# sensor_card.net
KiCad netlist of a schematic drawn in EAGLE
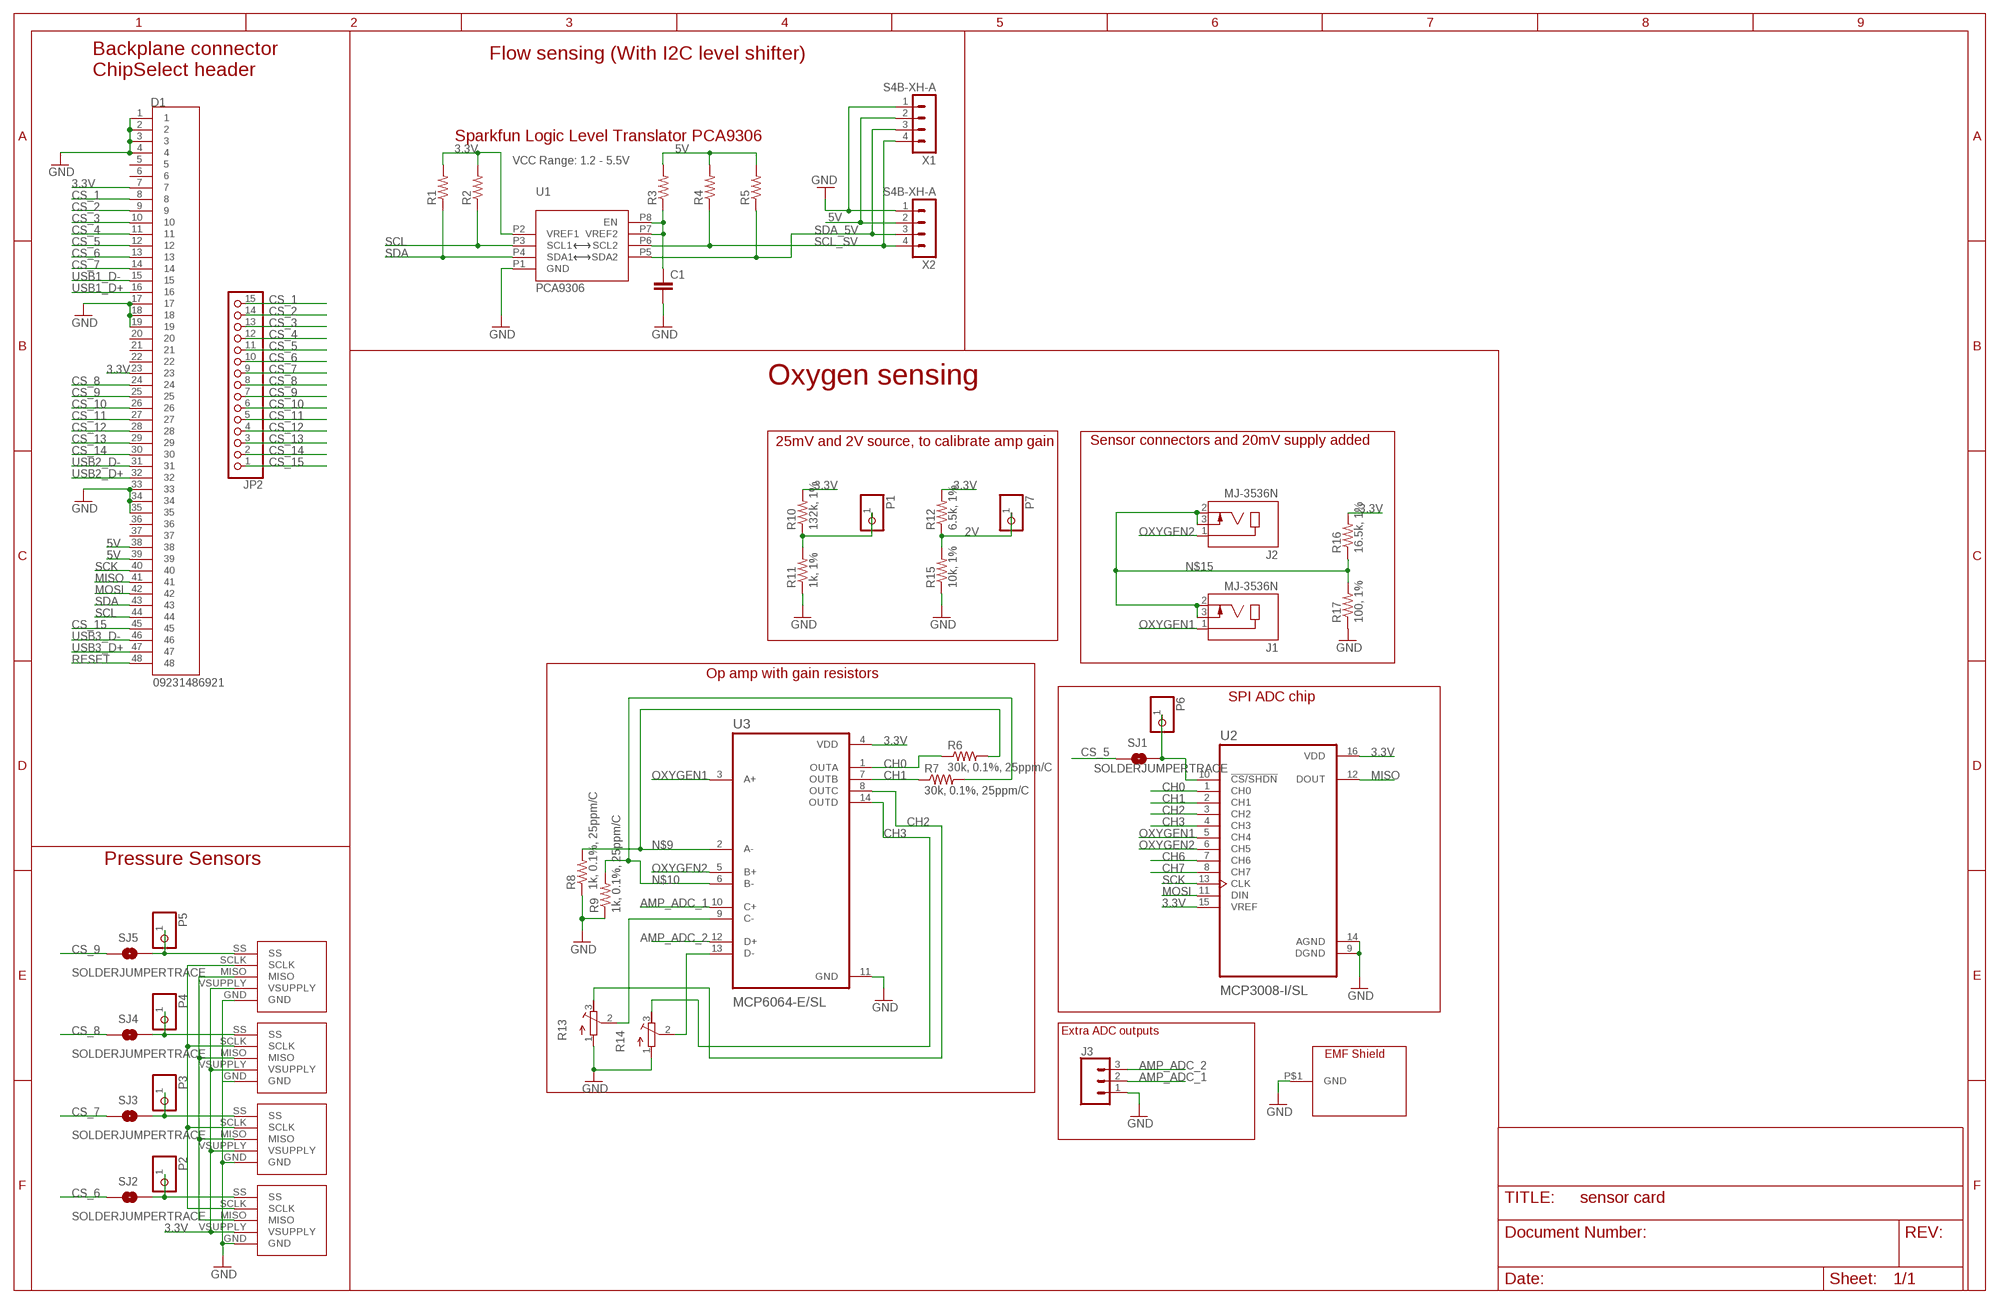
[diagram p0: schematic, sheet 1]

(export (version "E")
  (design (tool "Eeschema 10.0.6"))
  (components
    (comp (ref "C1")
      (value "100pF")
      (footprint "eagle-import:0805")
      (libsource (lib "eagle-import") (part "CAP0805"))
    )
    (comp (ref "D1")
      (value "09231486921")
      (footprint "eagle-import:HARTING_09231486921")
      (libsource (lib "eagle-import") (part "09231486921"))
    )
    (comp (ref "J1")
      (value "MJ-3536N")
      (footprint "eagle-import:CUI_MJ-3536N")
      (libsource (lib "eagle-import") (part "MJ-3536N"))
    )
    (comp (ref "J2")
      (value "MJ-3536N")
      (footprint "eagle-import:CUI_MJ-3536N")
      (libsource (lib "eagle-import") (part "MJ-3536N"))
    )
    (comp (ref "J3")
      (value "CONN_03")
      (footprint "eagle-import:1X03")
      (libsource (lib "eagle-import") (part "CONN_03"))
    )
    (comp (ref "JP2")
      (value "PINHD-1X15")
      (footprint "eagle-import:1X15")
      (libsource (lib "eagle-import") (part "PINHD-1X15"))
    )
    (comp (ref "P1")
      (value "PINHD-1X1")
      (footprint "eagle-import:1X01")
      (libsource (lib "eagle-import") (part "PINHD-1X1"))
    )
    (comp (ref "P2")
      (value "PINHD-1X1")
      (footprint "eagle-import:1X01")
      (libsource (lib "eagle-import") (part "PINHD-1X1"))
    )
    (comp (ref "P3")
      (value "PINHD-1X1")
      (footprint "eagle-import:1X01")
      (libsource (lib "eagle-import") (part "PINHD-1X1"))
    )
    (comp (ref "P4")
      (value "PINHD-1X1")
      (footprint "eagle-import:1X01")
      (libsource (lib "eagle-import") (part "PINHD-1X1"))
    )
    (comp (ref "P5")
      (value "PINHD-1X1")
      (footprint "eagle-import:1X01")
      (libsource (lib "eagle-import") (part "PINHD-1X1"))
    )
    (comp (ref "P6")
      (value "PINHD-1X1")
      (footprint "eagle-import:1X01")
      (libsource (lib "eagle-import") (part "PINHD-1X1"))
    )
    (comp (ref "P7")
      (value "PINHD-1X1")
      (footprint "eagle-import:1X01")
      (libsource (lib "eagle-import") (part "PINHD-1X1"))
    )
    (comp (ref "R1")
      (value "2.2k")
      (footprint "eagle-import:0805")
      (libsource (lib "eagle-import") (part "RESISTOR0805-RES"))
    )
    (comp (ref "R2")
      (value "2.2k")
      (footprint "eagle-import:0805")
      (libsource (lib "eagle-import") (part "RESISTOR0805-RES"))
    )
    (comp (ref "R3")
      (value "200K")
      (footprint "eagle-import:0805")
      (libsource (lib "eagle-import") (part "RESISTOR0805-RES"))
    )
    (comp (ref "R4")
      (value "2.2k")
      (footprint "eagle-import:0805")
      (libsource (lib "eagle-import") (part "RESISTOR0805-RES"))
    )
    (comp (ref "R5")
      (value "2.2k")
      (footprint "eagle-import:0805")
      (libsource (lib "eagle-import") (part "RESISTOR0805-RES"))
    )
    (comp (ref "R6")
      (value "30k, 0.1%, 25ppm/C")
      (footprint "eagle-import:0805")
      (fields
        (field (name "MANUFACTURER-PART-NUMBER") "ERA-6ARB303V")
        (field (name "SIMILAR-COMPONENTS") "Vishay precision resistors or anything else that fits the spec")
      )
      (libsource (lib "eagle-import") (part "RESISTOR0805-RES"))
    )
    (comp (ref "R7")
      (value "30k, 0.1%, 25ppm/C")
      (footprint "eagle-import:0805")
      (fields (field (name "MANUFACTURER-PART-NUMBER") "ERA-6ARB303V"))
      (libsource (lib "eagle-import") (part "RESISTOR0805-RES"))
    )
    (comp (ref "R8")
      (value "1k, 0.1%, 25ppm/C")
      (footprint "eagle-import:0805")
      (fields
        (field (name "MANUFACTURER-PART-NUMBER") "ERA-6ARB102V")
        (field (name "SIMILAR-COMPONENTS") "Vishay precision resistors or anything else that fits the spec")
      )
      (libsource (lib "eagle-import") (part "RESISTOR0805-RES"))
    )
    (comp (ref "R9")
      (value "1k, 0.1%, 25ppm/C")
      (footprint "eagle-import:0805")
      (fields
        (field (name "MANUFACTURER-PART-NUMBER") "ERA-6ARB102V")
        (field (name "SIMILAR-COMPONENTS") "Vishay precision resistors or anything else that fits the spec")
      )
      (libsource (lib "eagle-import") (part "RESISTOR0805-RES"))
    )
    (comp (ref "R10")
      (value "132k, 1%")
      (footprint "eagle-import:0805")
      (libsource (lib "eagle-import") (part "RESISTOR0805-RES"))
    )
    (comp (ref "R11")
      (value "1k, 1%")
      (footprint "eagle-import:0805")
      (libsource (lib "eagle-import") (part "RESISTOR0805-RES"))
    )
    (comp (ref "R12")
      (value "6.5k, 1%")
      (footprint "eagle-import:0805")
      (libsource (lib "eagle-import") (part "RESISTOR0805-RES"))
    )
    (comp (ref "R13")
      (value "R-TRIMM3214W")
      (footprint "eagle-import:RTRIM3214W")
      (libsource (lib "eagle-import") (part "R-TRIMM3214W"))
    )
    (comp (ref "R14")
      (value "R-TRIMM3214W")
      (footprint "eagle-import:RTRIM3214W")
      (libsource (lib "eagle-import") (part "R-TRIMM3214W"))
    )
    (comp (ref "R15")
      (value "10k, 1%")
      (footprint "eagle-import:0805")
      (libsource (lib "eagle-import") (part "RESISTOR0805-RES"))
    )
    (comp (ref "R16")
      (value "16.5k, 1%")
      (footprint "eagle-import:0805")
      (fields (field (name "MANUFACTURER-PART-NUMBER") "RMCF0805FT16K5"))
      (libsource (lib "eagle-import") (part "RESISTOR0805-RES"))
    )
    (comp (ref "R17")
      (value "100, 1%")
      (footprint "eagle-import:0805")
      (fields (field (name "MANUFACTURER-PART-NUMBER") "RMCF0805FT100R"))
      (libsource (lib "eagle-import") (part "RESISTOR0805-RES"))
    )
    (comp (ref "SJ1")
      (value "SOLDERJUMPERTRACE")
      (footprint "eagle-import:SJ_2S-TRACE")
      (libsource (lib "eagle-import") (part "SOLDERJUMPERTRACE"))
    )
    (comp (ref "SJ2")
      (value "SOLDERJUMPERTRACE")
      (footprint "eagle-import:SJ_2S-TRACE")
      (libsource (lib "eagle-import") (part "SOLDERJUMPERTRACE"))
    )
    (comp (ref "SJ3")
      (value "SOLDERJUMPERTRACE")
      (footprint "eagle-import:SJ_2S-TRACE")
      (libsource (lib "eagle-import") (part "SOLDERJUMPERTRACE"))
    )
    (comp (ref "SJ4")
      (value "SOLDERJUMPERTRACE")
      (footprint "eagle-import:SJ_2S-TRACE")
      (libsource (lib "eagle-import") (part "SOLDERJUMPERTRACE"))
    )
    (comp (ref "SJ5")
      (value "SOLDERJUMPERTRACE")
      (footprint "eagle-import:SJ_2S-TRACE")
      (libsource (lib "eagle-import") (part "SOLDERJUMPERTRACE"))
    )
    (comp (ref "U$1")
      (value "SCCDRRV100MDSA3SSCDRRV100MDSA3")
      (footprint "eagle-import:DIP1270W53P254L1303H508Q8B")
      (libsource (lib "eagle-import") (part "SCCDRRV100MDSA3SSCDRRV100MDSA3"))
    )
    (comp (ref "U$2")
      (value "EMI_SHIELD")
      (footprint "eagle-import:3671250")
      (libsource (lib "eagle-import") (part "EMI_SHIELD"))
    )
    (comp (ref "U$3")
      (value "SCCDRRV100MDSA3SSCDRRV100MDSA3")
      (footprint "eagle-import:DIP1270W53P254L1303H508Q8B")
      (libsource (lib "eagle-import") (part "SCCDRRV100MDSA3SSCDRRV100MDSA3"))
    )
    (comp (ref "U$4")
      (value "SCCDRRV100MDSA3SSCDRRV100MDSA3")
      (footprint "eagle-import:DIP1270W53P254L1303H508Q8B")
      (libsource (lib "eagle-import") (part "SCCDRRV100MDSA3SSCDRRV100MDSA3"))
    )
    (comp (ref "U$5")
      (value "SCCDRRV100MDSA3SSCDRRV100MDSA3")
      (footprint "eagle-import:DIP1270W53P254L1303H508Q8B")
      (libsource (lib "eagle-import") (part "SCCDRRV100MDSA3SSCDRRV100MDSA3"))
    )
    (comp (ref "U1")
      (value "PCA9306")
      (footprint "eagle-import:VSSOP_8PIN")
      (libsource (lib "eagle-import") (part "PCA9306VSSOP_8PIN"))
    )
    (comp (ref "U2")
      (value "MCP3008-I/SL")
      (footprint "eagle-import:SOIC127P600X175-16N")
      (libsource (lib "eagle-import") (part "MCP3008-I/SL"))
    )
    (comp (ref "U3")
      (value "MCP6064-E/SL")
      (footprint "eagle-import:SOIC127P600X175-14N")
      (libsource (lib "eagle-import") (part "MCP6064-E/SL"))
    )
    (comp (ref "X1")
      (value "S4B-XH-A")
      (footprint "eagle-import:S4B-XH-A")
      (libsource (lib "eagle-import") (part "S4B-XH-A"))
    )
    (comp (ref "X2")
      (value "S4B-XH-A")
      (footprint "eagle-import:S4B-XH-A")
      (libsource (lib "eagle-import") (part "S4B-XH-A"))
    )
  )
  (nets
    (net (code "1") (name "/2V") (class "Default")
      (node (ref "P7") (pin "1") (pinfunction "1_1") (pintype "passive"))
      (node (ref "R12") (pin "1") (pinfunction "1_1") (pintype "passive"))
      (node (ref "R15") (pin "2") (pinfunction "2_2") (pintype "passive"))
    )
    (net (code "2") (name "/3.3V") (class "Default")
      (node (ref "D1") (pin "23") (pinfunction "23_23") (pintype "passive"))
      (node (ref "D1") (pin "7") (pinfunction "7_7") (pintype "passive"))
      (node (ref "R1") (pin "2") (pinfunction "2_2") (pintype "passive"))
      (node (ref "R10") (pin "2") (pinfunction "2_2") (pintype "passive"))
      (node (ref "R12") (pin "2") (pinfunction "2_2") (pintype "passive"))
      (node (ref "R16") (pin "2") (pinfunction "2_2") (pintype "passive"))
      (node (ref "R2") (pin "2") (pinfunction "2_2") (pintype "passive"))
      (node (ref "U$1") (pin "VSUPPLY") (pinfunction "VSUPPLY_VSUPPLY") (pintype "bidirectional"))
      (node (ref "U$3") (pin "VSUPPLY") (pinfunction "VSUPPLY_VSUPPLY") (pintype "bidirectional"))
      (node (ref "U$4") (pin "VSUPPLY") (pinfunction "VSUPPLY_VSUPPLY") (pintype "bidirectional"))
      (node (ref "U$5") (pin "VSUPPLY") (pinfunction "VSUPPLY_VSUPPLY") (pintype "bidirectional"))
      (node (ref "U1") (pin "P2") (pinfunction "VREF1_P2") (pintype "power_in"))
      (node (ref "U2") (pin "15") (pinfunction "VREF_15") (pintype "input"))
      (node (ref "U2") (pin "16") (pinfunction "VDD_16") (pintype "power_in"))
      (node (ref "U3") (pin "4") (pinfunction "VDD_4") (pintype "power_in"))
    )
    (net (code "3") (name "/5V") (class "Default")
      (node (ref "D1") (pin "38") (pinfunction "38_38") (pintype "passive"))
      (node (ref "D1") (pin "39") (pinfunction "39_39") (pintype "passive"))
      (node (ref "R3") (pin "2") (pinfunction "2_2") (pintype "passive"))
      (node (ref "R4") (pin "2") (pinfunction "2_2") (pintype "passive"))
      (node (ref "R5") (pin "2") (pinfunction "2_2") (pintype "passive"))
      (node (ref "X1") (pin "2") (pinfunction "2_2") (pintype "passive"))
      (node (ref "X2") (pin "2") (pinfunction "2_2") (pintype "passive"))
    )
    (net (code "4") (name "/AMP_ADC_1") (class "Default")
      (node (ref "J3") (pin "2") (pinfunction "2_2") (pintype "passive"))
      (node (ref "U3") (pin "10") (pinfunction "C+_10") (pintype "bidirectional"))
    )
    (net (code "5") (name "/AMP_ADC_2") (class "Default")
      (node (ref "J3") (pin "3") (pinfunction "3_3") (pintype "passive"))
      (node (ref "U3") (pin "12") (pinfunction "D+_12") (pintype "bidirectional"))
    )
    (net (code "6") (name "/CH0") (class "Default")
      (node (ref "R6") (pin "1") (pinfunction "1_1") (pintype "passive"))
      (node (ref "U2") (pin "1") (pinfunction "CH0_1") (pintype "input"))
      (node (ref "U3") (pin "1") (pinfunction "OUTA_1") (pintype "output"))
    )
    (net (code "7") (name "/CH1") (class "Default")
      (node (ref "R7") (pin "1") (pinfunction "1_1") (pintype "passive"))
      (node (ref "U2") (pin "2") (pinfunction "CH1_2") (pintype "input"))
      (node (ref "U3") (pin "7") (pinfunction "OUTB_7") (pintype "output"))
    )
    (net (code "8") (name "/CH2") (class "Default")
      (node (ref "R13") (pin "3") (pinfunction "E_3") (pintype "passive"))
      (node (ref "U2") (pin "3") (pinfunction "CH2_3") (pintype "input"))
      (node (ref "U3") (pin "8") (pinfunction "OUTC_8") (pintype "output"))
    )
    (net (code "9") (name "/CH3") (class "Default")
      (node (ref "R14") (pin "3") (pinfunction "E_3") (pintype "passive"))
      (node (ref "U2") (pin "4") (pinfunction "CH3_4") (pintype "input"))
      (node (ref "U3") (pin "14") (pinfunction "OUTD_14") (pintype "output"))
    )
    (net (code "10") (name "/CH6") (class "Default")
      (node (ref "U2") (pin "7") (pinfunction "CH6_7") (pintype "input"))
    )
    (net (code "11") (name "/CH7") (class "Default")
      (node (ref "U2") (pin "8") (pinfunction "CH7_8") (pintype "input"))
    )
    (net (code "12") (name "/CS_1") (class "Default")
      (node (ref "D1") (pin "8") (pinfunction "8_8") (pintype "passive"))
      (node (ref "JP2") (pin "15") (pinfunction "15_15") (pintype "passive"))
    )
    (net (code "13") (name "/CS_2") (class "Default")
      (node (ref "D1") (pin "9") (pinfunction "9_9") (pintype "passive"))
      (node (ref "JP2") (pin "14") (pinfunction "14_14") (pintype "passive"))
    )
    (net (code "14") (name "/CS_3") (class "Default")
      (node (ref "D1") (pin "10") (pinfunction "10_10") (pintype "passive"))
      (node (ref "JP2") (pin "13") (pinfunction "13_13") (pintype "passive"))
    )
    (net (code "15") (name "/CS_4") (class "Default")
      (node (ref "D1") (pin "11") (pinfunction "11_11") (pintype "passive"))
      (node (ref "JP2") (pin "12") (pinfunction "12_12") (pintype "passive"))
    )
    (net (code "16") (name "/CS_5") (class "Default")
      (node (ref "D1") (pin "12") (pinfunction "12_12") (pintype "passive"))
      (node (ref "JP2") (pin "11") (pinfunction "11_11") (pintype "passive"))
      (node (ref "SJ1") (pin "1") (pinfunction "1_1") (pintype "passive"))
    )
    (net (code "17") (name "/CS_6") (class "Default")
      (node (ref "D1") (pin "13") (pinfunction "13_13") (pintype "passive"))
      (node (ref "JP2") (pin "10") (pinfunction "10_10") (pintype "passive"))
      (node (ref "SJ2") (pin "1") (pinfunction "1_1") (pintype "passive"))
    )
    (net (code "18") (name "/CS_7") (class "Default")
      (node (ref "D1") (pin "14") (pinfunction "14_14") (pintype "passive"))
      (node (ref "JP2") (pin "9") (pinfunction "9_9") (pintype "passive"))
      (node (ref "SJ3") (pin "1") (pinfunction "1_1") (pintype "passive"))
    )
    (net (code "19") (name "/CS_8") (class "Default")
      (node (ref "D1") (pin "24") (pinfunction "24_24") (pintype "passive"))
      (node (ref "JP2") (pin "8") (pinfunction "8_8") (pintype "passive"))
      (node (ref "SJ4") (pin "1") (pinfunction "1_1") (pintype "passive"))
    )
    (net (code "20") (name "/CS_9") (class "Default")
      (node (ref "D1") (pin "25") (pinfunction "25_25") (pintype "passive"))
      (node (ref "JP2") (pin "7") (pinfunction "7_7") (pintype "passive"))
      (node (ref "SJ5") (pin "1") (pinfunction "1_1") (pintype "passive"))
    )
    (net (code "21") (name "/CS_10") (class "Default")
      (node (ref "D1") (pin "26") (pinfunction "26_26") (pintype "passive"))
      (node (ref "JP2") (pin "6") (pinfunction "6_6") (pintype "passive"))
    )
    (net (code "22") (name "/CS_11") (class "Default")
      (node (ref "D1") (pin "27") (pinfunction "27_27") (pintype "passive"))
      (node (ref "JP2") (pin "5") (pinfunction "5_5") (pintype "passive"))
    )
    (net (code "23") (name "/CS_12") (class "Default")
      (node (ref "D1") (pin "28") (pinfunction "28_28") (pintype "passive"))
      (node (ref "JP2") (pin "4") (pinfunction "4_4") (pintype "passive"))
    )
    (net (code "24") (name "/CS_13") (class "Default")
      (node (ref "D1") (pin "29") (pinfunction "29_29") (pintype "passive"))
      (node (ref "JP2") (pin "3") (pinfunction "3_3") (pintype "passive"))
    )
    (net (code "25") (name "/CS_14") (class "Default")
      (node (ref "D1") (pin "30") (pinfunction "30_30") (pintype "passive"))
      (node (ref "JP2") (pin "2") (pinfunction "2_2") (pintype "passive"))
    )
    (net (code "26") (name "/CS_15") (class "Default")
      (node (ref "D1") (pin "45") (pinfunction "45_45") (pintype "passive"))
      (node (ref "JP2") (pin "1") (pinfunction "1_1") (pintype "passive"))
    )
    (net (code "27") (name "/MISO") (class "Default")
      (node (ref "D1") (pin "41") (pinfunction "41_41") (pintype "passive"))
      (node (ref "U$1") (pin "MISO") (pinfunction "MISO_MISO") (pintype "bidirectional"))
      (node (ref "U$3") (pin "MISO") (pinfunction "MISO_MISO") (pintype "bidirectional"))
      (node (ref "U$4") (pin "MISO") (pinfunction "MISO_MISO") (pintype "bidirectional"))
      (node (ref "U$5") (pin "MISO") (pinfunction "MISO_MISO") (pintype "bidirectional"))
      (node (ref "U2") (pin "12") (pinfunction "DOUT_12") (pintype "output"))
    )
    (net (code "28") (name "/MOSI") (class "Default")
      (node (ref "D1") (pin "42") (pinfunction "42_42") (pintype "passive"))
      (node (ref "U2") (pin "11") (pinfunction "DIN_11") (pintype "input"))
    )
    (net (code "29") (name "/N$9") (class "Default")
      (node (ref "R6") (pin "2") (pinfunction "2_2") (pintype "passive"))
      (node (ref "R8") (pin "2") (pinfunction "2_2") (pintype "passive"))
      (node (ref "U3") (pin "2") (pinfunction "A-_2") (pintype "bidirectional"))
    )
    (net (code "30") (name "/N$10") (class "Default")
      (node (ref "R7") (pin "2") (pinfunction "2_2") (pintype "passive"))
      (node (ref "R9") (pin "2") (pinfunction "2_2") (pintype "passive"))
      (node (ref "U3") (pin "6") (pinfunction "B-_6") (pintype "bidirectional"))
    )
    (net (code "31") (name "/N$15") (class "Default")
      (node (ref "J1") (pin "2") (pinfunction "2_2") (pintype "passive"))
      (node (ref "J1") (pin "3") (pinfunction "3_3") (pintype "passive"))
      (node (ref "J2") (pin "2") (pinfunction "2_2") (pintype "passive"))
      (node (ref "J2") (pin "3") (pinfunction "3_3") (pintype "passive"))
      (node (ref "R16") (pin "1") (pinfunction "1_1") (pintype "passive"))
      (node (ref "R17") (pin "2") (pinfunction "2_2") (pintype "passive"))
    )
    (net (code "32") (name "/OXYGEN1") (class "Default")
      (node (ref "J1") (pin "1") (pinfunction "1_1") (pintype "passive"))
      (node (ref "U2") (pin "5") (pinfunction "CH4_5") (pintype "input"))
      (node (ref "U3") (pin "3") (pinfunction "A+_3") (pintype "bidirectional"))
    )
    (net (code "33") (name "/OXYGEN2") (class "Default")
      (node (ref "J2") (pin "1") (pinfunction "1_1") (pintype "passive"))
      (node (ref "U2") (pin "6") (pinfunction "CH5_6") (pintype "input"))
      (node (ref "U3") (pin "5") (pinfunction "B+_5") (pintype "bidirectional"))
    )
    (net (code "34") (name "/RESET") (class "Default")
      (node (ref "D1") (pin "48") (pinfunction "48_48") (pintype "passive"))
    )
    (net (code "35") (name "/SCK") (class "Default")
      (node (ref "D1") (pin "40") (pinfunction "40_40") (pintype "passive"))
      (node (ref "U$1") (pin "SCLK") (pinfunction "SCLK_SCLK") (pintype "bidirectional"))
      (node (ref "U$3") (pin "SCLK") (pinfunction "SCLK_SCLK") (pintype "bidirectional"))
      (node (ref "U$4") (pin "SCLK") (pinfunction "SCLK_SCLK") (pintype "bidirectional"))
      (node (ref "U$5") (pin "SCLK") (pinfunction "SCLK_SCLK") (pintype "bidirectional"))
      (node (ref "U2") (pin "13") (pinfunction "CLK_13") (pintype "input"))
    )
    (net (code "36") (name "/SCL") (class "Default")
      (node (ref "D1") (pin "44") (pinfunction "44_44") (pintype "passive"))
      (node (ref "R2") (pin "1") (pinfunction "1_1") (pintype "passive"))
      (node (ref "U1") (pin "P3") (pinfunction "SCL1_P3") (pintype "bidirectional"))
    )
    (net (code "37") (name "/SCL_SV") (class "Default")
      (node (ref "R4") (pin "1") (pinfunction "1_1") (pintype "passive"))
      (node (ref "U1") (pin "P6") (pinfunction "SCL2_P6") (pintype "bidirectional"))
      (node (ref "X1") (pin "4") (pinfunction "4_4") (pintype "passive"))
      (node (ref "X2") (pin "4") (pinfunction "4_4") (pintype "passive"))
    )
    (net (code "38") (name "/SDA") (class "Default")
      (node (ref "D1") (pin "43") (pinfunction "43_43") (pintype "passive"))
      (node (ref "R1") (pin "1") (pinfunction "1_1") (pintype "passive"))
      (node (ref "U1") (pin "P4") (pinfunction "SDA1_P4") (pintype "bidirectional"))
    )
    (net (code "39") (name "/SDA_5V") (class "Default")
      (node (ref "R5") (pin "1") (pinfunction "1_1") (pintype "passive"))
      (node (ref "U1") (pin "P5") (pinfunction "SDA2_P5") (pintype "bidirectional"))
      (node (ref "X1") (pin "3") (pinfunction "3_3") (pintype "passive"))
      (node (ref "X2") (pin "3") (pinfunction "3_3") (pintype "passive"))
    )
    (net (code "40") (name "/USB1_D+") (class "Default")
      (node (ref "D1") (pin "16") (pinfunction "16_16") (pintype "passive"))
    )
    (net (code "41") (name "/USB1_D-") (class "Default")
      (node (ref "D1") (pin "15") (pinfunction "15_15") (pintype "passive"))
    )
    (net (code "42") (name "/USB2_D+") (class "Default")
      (node (ref "D1") (pin "32") (pinfunction "32_32") (pintype "passive"))
    )
    (net (code "43") (name "/USB2_D-") (class "Default")
      (node (ref "D1") (pin "31") (pinfunction "31_31") (pintype "passive"))
    )
    (net (code "44") (name "/USB3_D+") (class "Default")
      (node (ref "D1") (pin "47") (pinfunction "47_47") (pintype "passive"))
    )
    (net (code "45") (name "/USB3_D-") (class "Default")
      (node (ref "D1") (pin "46") (pinfunction "46_46") (pintype "passive"))
    )
    (net (code "46") (name "GND") (class "Default")
      (node (ref "C1") (pin "2") (pinfunction "2_2") (pintype "passive"))
      (node (ref "D1") (pin "1") (pinfunction "1_1") (pintype "passive"))
      (node (ref "D1") (pin "17") (pinfunction "17_17") (pintype "passive"))
      (node (ref "D1") (pin "18") (pinfunction "18_18") (pintype "passive"))
      (node (ref "D1") (pin "19") (pinfunction "19_19") (pintype "passive"))
      (node (ref "D1") (pin "2") (pinfunction "2_2") (pintype "passive"))
      (node (ref "D1") (pin "3") (pinfunction "3_3") (pintype "passive"))
      (node (ref "D1") (pin "33") (pinfunction "33_33") (pintype "passive"))
      (node (ref "D1") (pin "34") (pinfunction "34_34") (pintype "passive"))
      (node (ref "D1") (pin "35") (pinfunction "35_35") (pintype "passive"))
      (node (ref "D1") (pin "4") (pinfunction "4_4") (pintype "passive"))
      (node (ref "J3") (pin "1") (pinfunction "1_1") (pintype "passive"))
      (node (ref "R11") (pin "1") (pinfunction "1_1") (pintype "passive"))
      (node (ref "R13") (pin "1") (pinfunction "A_1") (pintype "passive"))
      (node (ref "R14") (pin "1") (pinfunction "A_1") (pintype "passive"))
      (node (ref "R15") (pin "1") (pinfunction "1_1") (pintype "passive"))
      (node (ref "R17") (pin "1") (pinfunction "1_1") (pintype "passive"))
      (node (ref "R8") (pin "1") (pinfunction "1_1") (pintype "passive"))
      (node (ref "R9") (pin "1") (pinfunction "1_1") (pintype "passive"))
      (node (ref "U$1") (pin "GND") (pinfunction "GND_GND") (pintype "bidirectional"))
      (node (ref "U$2") (pin "P$1") (pinfunction "GND_P$1") (pintype "bidirectional"))
      (node (ref "U$3") (pin "GND") (pinfunction "GND_GND") (pintype "bidirectional"))
      (node (ref "U$4") (pin "GND") (pinfunction "GND_GND") (pintype "bidirectional"))
      (node (ref "U$5") (pin "GND") (pinfunction "GND_GND") (pintype "bidirectional"))
      (node (ref "U1") (pin "P1") (pinfunction "GND_P1") (pintype "power_in"))
      (node (ref "U2") (pin "14") (pinfunction "AGND_14") (pintype "power_in"))
      (node (ref "U2") (pin "9") (pinfunction "DGND_9") (pintype "power_in"))
      (node (ref "U3") (pin "11") (pinfunction "GND_11") (pintype "power_in"))
      (node (ref "X1") (pin "1") (pinfunction "1_1") (pintype "passive"))
      (node (ref "X2") (pin "1") (pinfunction "1_1") (pintype "passive"))
    )
    (net (code "47") (name "Net-(P1-Pad1)") (class "Default")
      (node (ref "P1") (pin "1") (pinfunction "1_1") (pintype "passive"))
      (node (ref "R10") (pin "1") (pinfunction "1_1") (pintype "passive"))
      (node (ref "R11") (pin "2") (pinfunction "2_2") (pintype "passive"))
    )
    (net (code "48") (name "Net-(P2-Pad1)") (class "Default")
      (node (ref "P2") (pin "1") (pinfunction "1_1") (pintype "passive"))
      (node (ref "SJ2") (pin "2") (pinfunction "2_2") (pintype "passive"))
      (node (ref "U$5") (pin "SS") (pinfunction "SS_SS") (pintype "bidirectional"))
    )
    (net (code "49") (name "Net-(P3-Pad1)") (class "Default")
      (node (ref "P3") (pin "1") (pinfunction "1_1") (pintype "passive"))
      (node (ref "SJ3") (pin "2") (pinfunction "2_2") (pintype "passive"))
      (node (ref "U$4") (pin "SS") (pinfunction "SS_SS") (pintype "bidirectional"))
    )
    (net (code "50") (name "Net-(P4-Pad1)") (class "Default")
      (node (ref "P4") (pin "1") (pinfunction "1_1") (pintype "passive"))
      (node (ref "SJ4") (pin "2") (pinfunction "2_2") (pintype "passive"))
      (node (ref "U$3") (pin "SS") (pinfunction "SS_SS") (pintype "bidirectional"))
    )
    (net (code "51") (name "Net-(P5-Pad1)") (class "Default")
      (node (ref "P5") (pin "1") (pinfunction "1_1") (pintype "passive"))
      (node (ref "SJ5") (pin "2") (pinfunction "2_2") (pintype "passive"))
      (node (ref "U$1") (pin "SS") (pinfunction "SS_SS") (pintype "bidirectional"))
    )
    (net (code "52") (name "Net-(R13-S)") (class "Default")
      (node (ref "R13") (pin "2") (pinfunction "S_2") (pintype "passive"))
      (node (ref "U3") (pin "9") (pinfunction "C-_9") (pintype "bidirectional"))
    )
    (net (code "53") (name "Net-(R14-S)") (class "Default")
      (node (ref "R14") (pin "2") (pinfunction "S_2") (pintype "passive"))
      (node (ref "U3") (pin "13") (pinfunction "D-_13") (pintype "bidirectional"))
    )
    (net (code "54") (name "Net-(U1-EN)") (class "Default")
      (node (ref "C1") (pin "1") (pinfunction "1_1") (pintype "passive"))
      (node (ref "R3") (pin "1") (pinfunction "1_1") (pintype "passive"))
      (node (ref "U1") (pin "P7") (pinfunction "VREF2_P7") (pintype "power_in"))
      (node (ref "U1") (pin "P8") (pinfunction "EN_P8") (pintype "input"))
    )
    (net (code "55") (name "Net-(U2-~{CS{slash}SHDN})") (class "Default")
      (node (ref "P6") (pin "1") (pinfunction "1_1") (pintype "passive"))
      (node (ref "SJ1") (pin "2") (pinfunction "2_2") (pintype "passive"))
      (node (ref "U2") (pin "10") (pinfunction "~{CS/SHDN}_10") (pintype "input"))
    )
    (net (code "56") (name "unconnected-(D1-Pad5)") (class "Default")
      (node (ref "D1") (pin "5") (pinfunction "5_5") (pintype "passive"))
    )
    (net (code "57") (name "unconnected-(D1-Pad6)") (class "Default")
      (node (ref "D1") (pin "6") (pinfunction "6_6") (pintype "passive"))
    )
    (net (code "58") (name "unconnected-(D1-Pad20)") (class "Default")
      (node (ref "D1") (pin "20") (pinfunction "20_20") (pintype "passive"))
    )
    (net (code "59") (name "unconnected-(D1-Pad21)") (class "Default")
      (node (ref "D1") (pin "21") (pinfunction "21_21") (pintype "passive"))
    )
    (net (code "60") (name "unconnected-(D1-Pad22)") (class "Default")
      (node (ref "D1") (pin "22") (pinfunction "22_22") (pintype "passive"))
    )
    (net (code "61") (name "unconnected-(D1-Pad36)") (class "Default")
      (node (ref "D1") (pin "36") (pinfunction "36_36") (pintype "passive"))
    )
    (net (code "62") (name "unconnected-(D1-Pad37)") (class "Default")
      (node (ref "D1") (pin "37") (pinfunction "37_37") (pintype "passive"))
    )
  )
)
